# POWER.net
KiCad netlist of a schematic drawn in Altium Designer
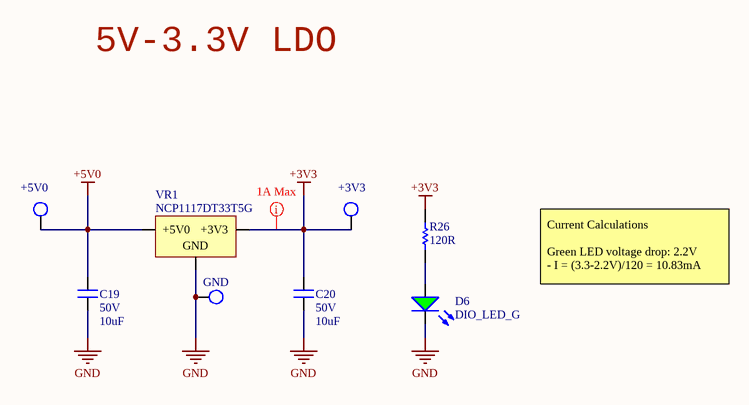
[diagram p0: POWER.SchDoc]

(export (version "E")
  (design (tool "Eeschema 10.0.6"))
  (components
    (comp (ref "+3V3")
      (value "TESTPOINT_LOOP")
      (footprint "TESTPOINT_LOOP")
      (description "Loop testpoint through-hole pad")
      (fields (field (name "MANUFACTURER") "Keystone Electronics"))
      (libsource (lib "UWRT_Schematic_Library_2020") (part "TESTPOINT_LOOP"))
    )
    (comp (ref "+5V0")
      (value "TESTPOINT_LOOP")
      (footprint "TESTPOINT_LOOP")
      (description "Loop testpoint through-hole pad")
      (fields (field (name "MANUFACTURER") "Keystone Electronics"))
      (libsource (lib "") (part "TESTPOINT_LOOP_1"))
    )
    (comp (ref "C19")
      (value "10uF")
      (footprint "CAPC1206(3216)")
      (description "CAP CER 10UF 50V X5R 1206")
      (fields
        (field (name "MPN") "GRT31CR61H106KE01L")
        (field (name "MANUFACTURER") "Murata")
        (field (name "VOLTAGE RATING") "50V")
      )
      (libsource (lib "UWRT_Schematic_Library_2020") (part "CAP_10uF_50V_1206"))
    )
    (comp (ref "C20")
      (value "10uF")
      (footprint "CAPC1206(3216)")
      (description "CAP CER 10UF 50V X5R 1206")
      (fields
        (field (name "MPN") "GRT31CR61H106KE01L")
        (field (name "MANUFACTURER") "Murata")
        (field (name "VOLTAGE RATING") "50V")
      )
      (libsource (lib "UWRT_Schematic_Library_2020") (part "CAP_10uF_50V_1206"))
    )
    (comp (ref "D6")
      (value "DIO_LED_G")
      (footprint "LED_0805_LINE")
      (description "LED GREEN DIFFUSED 0805 SMD")
      (fields (field (name "MPN") "LG R971-KN-1") (field (name "MANUFACTURER") "OSRAM"))
      (libsource (lib "UWRT_Schematic_Library_2020") (part "DIO_LED_G"))
    )
    (comp (ref "GND")
      (value "TESTPOINT_LOOP")
      (footprint "TESTPOINT_LOOP")
      (description "Loop testpoint through-hole pad")
      (fields (field (name "MANUFACTURER") "Keystone Electronics"))
      (libsource (lib "UWRT_Schematic_Library_2020") (part "TESTPOINT_LOOP"))
    )
    (comp (ref "R26")
      (value "120R")
      (footprint "RESC0603(1608)_N")
      (description "RES SMD 120 OHM 5% 1/10W 0603")
      (fields (field (name "MANUFACTURER") "Yageo") (field (name "MPN") "RC0603JR-07120RL"))
      (libsource (lib "UWRT_Schematic_Library_2020") (part "RES_120R_0603"))
    )
    (comp (ref "VR1")
      (value "5V0_3V3_LDO")
      (footprint "VOLTAGE_REGULATOR")
      (description "IC REG LINEAR 3.3V 1A DPAK")
      (fields (field (name "MPN") "NCP1117DT33T5G") (field (name "MANUFACTURER") "ON Semiconductor"))
      (libsource (lib "UWRT_Schematic_Library_2020") (part "5V0_3V3_LDO"))
    )
  )
  (nets
    (net (code "1") (name "+3V3") (class "Default")
      (node (ref "+3V3") (pin "1") (pintype "passive"))
      (node (ref "C20") (pin "1") (pinfunction "1_1") (pintype "passive"))
      (node (ref "R26") (pin "2") (pinfunction "2_2") (pintype "passive"))
      (node (ref "VR1") (pin "2") (pinfunction "+3V3_2") (pintype "passive"))
    )
    (net (code "2") (name "+5V0") (class "Default")
      (node (ref "C19") (pin "1") (pinfunction "1_1") (pintype "passive"))
      (node (ref "VR1") (pin "3") (pinfunction "+5V0_3") (pintype "passive"))
    )
    (net (code "3") (name "GND") (class "Default")
      (node (ref "C19") (pin "2") (pinfunction "2_2") (pintype "passive"))
      (node (ref "C20") (pin "2") (pinfunction "2_2") (pintype "passive"))
      (node (ref "D6") (pin "2") (pinfunction "K_2") (pintype "passive"))
      (node (ref "GND") (pin "1") (pintype "passive"))
      (node (ref "VR1") (pin "1") (pinfunction "GND_1") (pintype "passive"))
    )
    (net (code "4") (name "Net-(D6-A)") (class "Default")
      (node (ref "D6") (pin "1") (pinfunction "A_1") (pintype "passive"))
      (node (ref "R26") (pin "1") (pinfunction "1_1") (pintype "passive"))
    )
    (net (code "5") (name "unconnected-(+5V0-Pad1)") (class "Default")
      (node (ref "+5V0") (pin "1") (pintype "passive"))
    )
  )
)
